# KitchenExhaustFan.net
KiCad netlist of a schematic drawn in EasyEDA
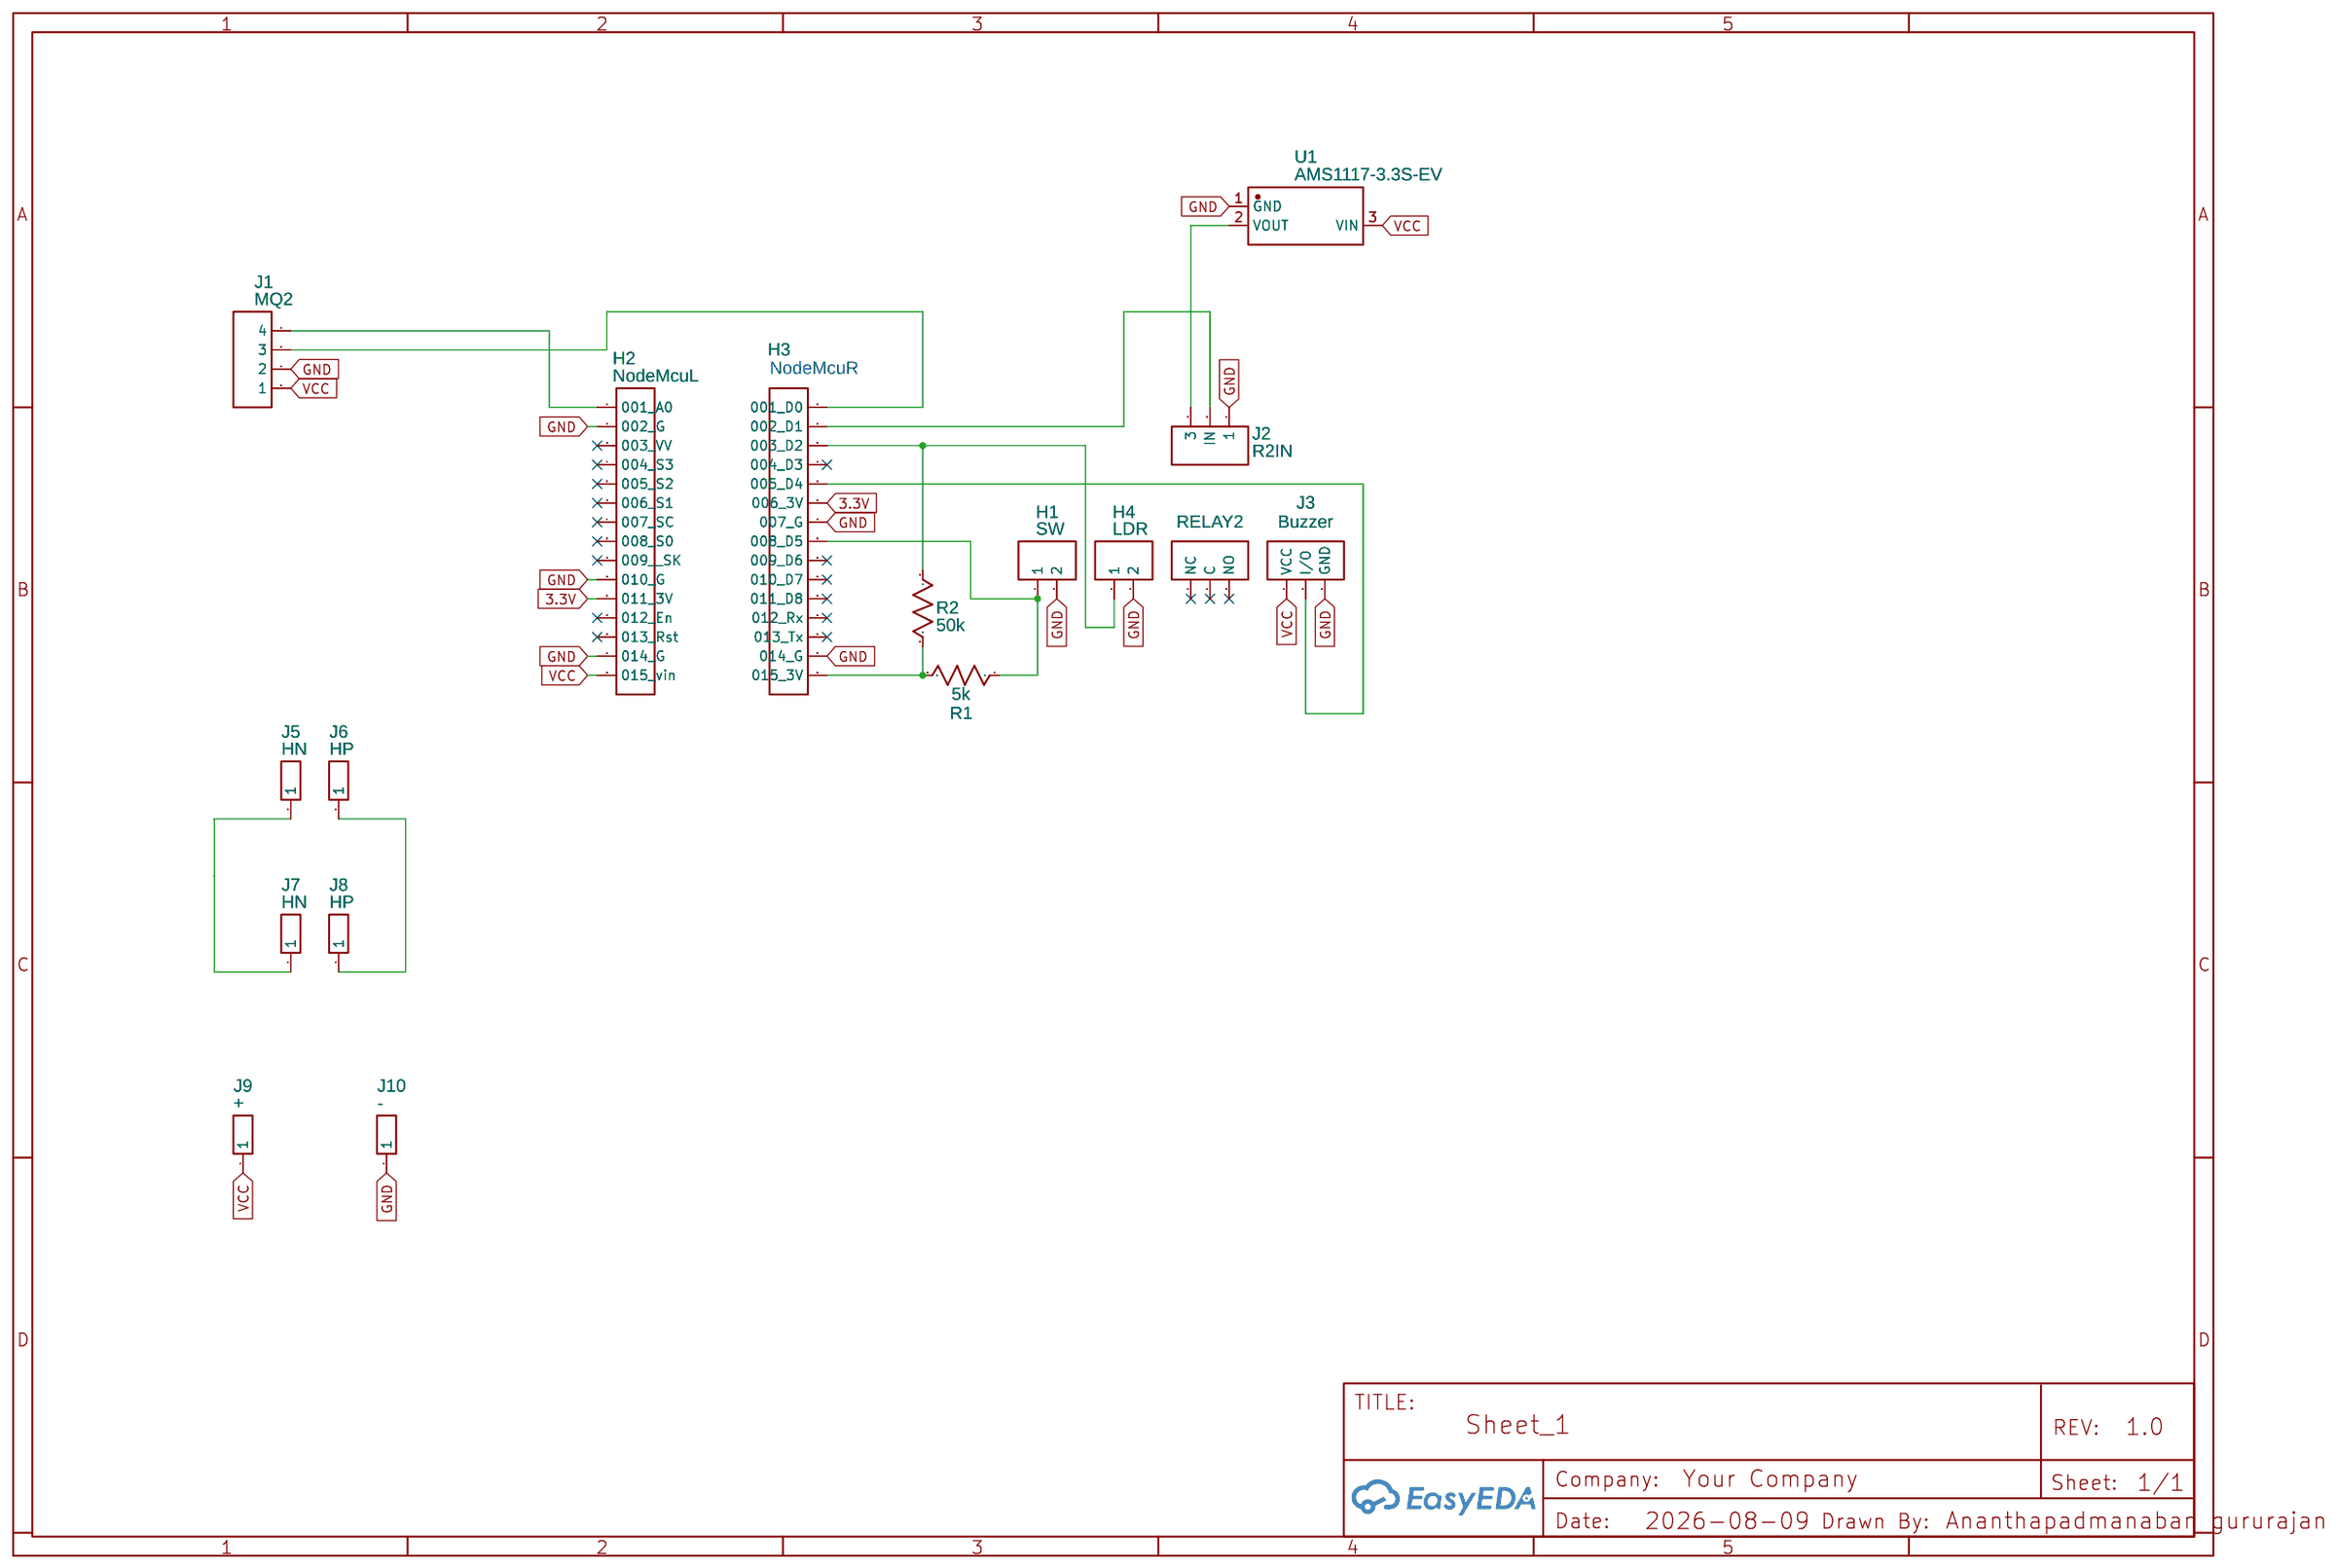
[diagram p0: schematic sheet]

(export (version "E")
  (design (tool "Eeschema 10.0.6"))
  (components
    (comp (ref "H1") (value "SW") (libsource (lib "") (part "HDR-F-2.54_1x2")))
    (comp (ref "H2") (value "NodeMcuL") (libsource (lib "") (part "HDR-F-2.54_1x15")))
    (comp (ref "H3") (value "NodeMcuR") (libsource (lib "") (part "HDR-F-2.54_1x15_1")))
    (comp (ref "H4") (value "LDR") (libsource (lib "") (part "HDR-F-2.54_1x2")))
    (comp (ref "J1") (value "MQ2") (libsource (lib "") (part "HDR-M-2.54_1x4")))
    (comp (ref "J2") (value "R2IN") (libsource (lib "") (part "HDR-M-2.54_1x3_1")))
    (comp (ref "J3") (value "Buzzer") (libsource (lib "") (part "HDR-M-2.54_1x3")))
    (comp (ref "J5") (value "HN") (libsource (lib "") (part "HDR-M-2.54_1x1")))
    (comp (ref "J6") (value "HP") (libsource (lib "") (part "HDR-M-2.54_1x1")))
    (comp (ref "J7") (value "HN") (libsource (lib "") (part "HDR-M-2.54_1x1")))
    (comp (ref "J8") (value "HP") (libsource (lib "") (part "HDR-M-2.54_1x1")))
    (comp (ref "J9") (value "+") (libsource (lib "") (part "HDR-M-2.54_1x1")))
    (comp (ref "J10") (value "-") (libsource (lib "") (part "HDR-M-2.54_1x1")))
    (comp (ref "R1") (value "5k") (libsource (lib "") (part "R_AXIAL-0.3_US_1")))
    (comp (ref "R2") (value "50k") (libsource (lib "") (part "R_AXIAL-0.3_US")))
    (comp (ref "RELAY2") (value "Relay1") (libsource (lib "") (part "HDR-M-2.54_1x3_2")))
    (comp (ref "U1") (value "AMS1117-3.3S-EV") (libsource (lib "") (part "AMS1117-3.3S-EV")))
  )
  (nets
    (net (code "1") (name "3.3V") (class "Default")
      (node (ref "H2") (pin "11") (pinfunction "011_3V_11") (pintype "unspecified"))
      (node (ref "H3") (pin "6") (pinfunction "006_3V_6") (pintype "unspecified"))
    )
    (net (code "2") (name "GND") (class "Default")
      (node (ref "H1") (pin "2") (pinfunction "2_2") (pintype "input"))
      (node (ref "H2") (pin "10") (pinfunction "010_G_10") (pintype "unspecified"))
      (node (ref "H2") (pin "14") (pinfunction "014_G_14") (pintype "unspecified"))
      (node (ref "H2") (pin "2") (pinfunction "002_G_2") (pintype "unspecified"))
      (node (ref "H3") (pin "14") (pinfunction "014_G_14") (pintype "unspecified"))
      (node (ref "H3") (pin "7") (pinfunction "007_G_7") (pintype "unspecified"))
      (node (ref "H4") (pin "2") (pinfunction "2_2") (pintype "input"))
      (node (ref "J1") (pin "2") (pinfunction "2_2") (pintype "unspecified"))
      (node (ref "J10") (pin "1") (pinfunction "1_1") (pintype "input"))
      (node (ref "J2") (pin "1") (pinfunction "1_1") (pintype "input"))
      (node (ref "J3") (pin "3") (pinfunction "GND_3") (pintype "input"))
      (node (ref "U1") (pin "1") (pinfunction "GND_1") (pintype "unspecified"))
    )
    (net (code "3") (name "Net-(H2-001_A0)") (class "Default")
      (node (ref "H2") (pin "1") (pinfunction "001_A0_1") (pintype "unspecified"))
      (node (ref "J1") (pin "4") (pinfunction "4_4") (pintype "unspecified"))
    )
    (net (code "4") (name "Net-(H3-001_D0)") (class "Default")
      (node (ref "H3") (pin "1") (pinfunction "001_D0_1") (pintype "unspecified"))
      (node (ref "J1") (pin "3") (pinfunction "3_3") (pintype "unspecified"))
    )
    (net (code "5") (name "Net-(H3-002_D1)") (class "Default")
      (node (ref "H3") (pin "2") (pinfunction "002_D1_2") (pintype "unspecified"))
      (node (ref "J2") (pin "2") (pinfunction "IN_2") (pintype "input"))
    )
    (net (code "6") (name "Net-(H3-003_D2)") (class "Default")
      (node (ref "H3") (pin "3") (pinfunction "003_D2_3") (pintype "unspecified"))
      (node (ref "H4") (pin "1") (pinfunction "1_1") (pintype "input"))
      (node (ref "R2") (pin "1") (pinfunction "1_1") (pintype "unspecified"))
    )
    (net (code "7") (name "Net-(H3-005_D4)") (class "Default")
      (node (ref "H3") (pin "5") (pinfunction "005_D4_5") (pintype "unspecified"))
      (node (ref "J3") (pin "2") (pinfunction "I/O_2") (pintype "input"))
    )
    (net (code "8") (name "Net-(H3-008_D5)") (class "Default")
      (node (ref "H1") (pin "1") (pinfunction "1_1") (pintype "input"))
      (node (ref "H3") (pin "8") (pinfunction "008_D5_8") (pintype "unspecified"))
      (node (ref "R1") (pin "1") (pinfunction "1_1") (pintype "unspecified"))
    )
    (net (code "9") (name "Net-(H3-015_3V)") (class "Default")
      (node (ref "H3") (pin "15") (pinfunction "015_3V_15") (pintype "unspecified"))
      (node (ref "R1") (pin "2") (pinfunction "2_2") (pintype "unspecified"))
      (node (ref "R2") (pin "2") (pinfunction "2_2") (pintype "unspecified"))
    )
    (net (code "10") (name "Net-(J5-Pad1)") (class "Default")
      (node (ref "J5") (pin "1") (pinfunction "1_1") (pintype "input"))
      (node (ref "J7") (pin "1") (pinfunction "1_1") (pintype "input"))
    )
    (net (code "11") (name "Net-(J6-Pad1)") (class "Default")
      (node (ref "J6") (pin "1") (pinfunction "1_1") (pintype "input"))
      (node (ref "J8") (pin "1") (pinfunction "1_1") (pintype "input"))
    )
    (net (code "12") (name "Net-(U1-VOUT)") (class "Default")
      (node (ref "J2") (pin "3") (pinfunction "3_3") (pintype "input"))
      (node (ref "U1") (pin "2") (pinfunction "VOUT_2") (pintype "unspecified"))
    )
    (net (code "13") (name "VCC") (class "Default")
      (node (ref "H2") (pin "15") (pinfunction "015_vin_15") (pintype "unspecified"))
      (node (ref "J1") (pin "1") (pinfunction "1_1") (pintype "unspecified"))
      (node (ref "J3") (pin "1") (pinfunction "VCC_1") (pintype "input"))
      (node (ref "J9") (pin "1") (pinfunction "1_1") (pintype "input"))
      (node (ref "U1") (pin "3") (pinfunction "VIN_3") (pintype "unspecified"))
    )
    (net (code "14") (name "unconnected-(H2-003_VV-Pad3)") (class "Default")
      (node (ref "H2") (pin "3") (pinfunction "003_VV_3") (pintype "unspecified+no_connect"))
    )
    (net (code "15") (name "unconnected-(H2-004_S3-Pad4)") (class "Default")
      (node (ref "H2") (pin "4") (pinfunction "004_S3_4") (pintype "unspecified+no_connect"))
    )
    (net (code "16") (name "unconnected-(H2-005_S2-Pad5)") (class "Default")
      (node (ref "H2") (pin "5") (pinfunction "005_S2_5") (pintype "unspecified+no_connect"))
    )
    (net (code "17") (name "unconnected-(H2-006_S1-Pad6)") (class "Default")
      (node (ref "H2") (pin "6") (pinfunction "006_S1_6") (pintype "unspecified+no_connect"))
    )
    (net (code "18") (name "unconnected-(H2-007_SC-Pad7)") (class "Default")
      (node (ref "H2") (pin "7") (pinfunction "007_SC_7") (pintype "unspecified+no_connect"))
    )
    (net (code "19") (name "unconnected-(H2-008_S0-Pad8)") (class "Default")
      (node (ref "H2") (pin "8") (pinfunction "008_S0_8") (pintype "unspecified+no_connect"))
    )
    (net (code "20") (name "unconnected-(H2-009__SK-Pad9)") (class "Default")
      (node (ref "H2") (pin "9") (pinfunction "009__SK_9") (pintype "unspecified+no_connect"))
    )
    (net (code "21") (name "unconnected-(H2-012_En-Pad12)") (class "Default")
      (node (ref "H2") (pin "12") (pinfunction "012_En_12") (pintype "unspecified+no_connect"))
    )
    (net (code "22") (name "unconnected-(H2-013_Rst-Pad13)") (class "Default")
      (node (ref "H2") (pin "13") (pinfunction "013_Rst_13") (pintype "unspecified+no_connect"))
    )
    (net (code "23") (name "unconnected-(H3-004_D3-Pad4)") (class "Default")
      (node (ref "H3") (pin "4") (pinfunction "004_D3_4") (pintype "unspecified+no_connect"))
    )
    (net (code "24") (name "unconnected-(H3-009_D6-Pad9)") (class "Default")
      (node (ref "H3") (pin "9") (pinfunction "009_D6_9") (pintype "unspecified+no_connect"))
    )
    (net (code "25") (name "unconnected-(H3-010_D7-Pad10)") (class "Default")
      (node (ref "H3") (pin "10") (pinfunction "010_D7_10") (pintype "unspecified+no_connect"))
    )
    (net (code "26") (name "unconnected-(H3-011_D8-Pad11)") (class "Default")
      (node (ref "H3") (pin "11") (pinfunction "011_D8_11") (pintype "unspecified+no_connect"))
    )
    (net (code "27") (name "unconnected-(H3-012_Rx-Pad12)") (class "Default")
      (node (ref "H3") (pin "12") (pinfunction "012_Rx_12") (pintype "unspecified+no_connect"))
    )
    (net (code "28") (name "unconnected-(H3-013_Tx-Pad13)") (class "Default")
      (node (ref "H3") (pin "13") (pinfunction "013_Tx_13") (pintype "unspecified+no_connect"))
    )
    (net (code "29") (name "unconnected-(RELAY2-C-Pad2)") (class "Default")
      (node (ref "RELAY2") (pin "2") (pinfunction "C_2") (pintype "input+no_connect"))
    )
    (net (code "30") (name "unconnected-(RELAY2-NC-Pad1)") (class "Default")
      (node (ref "RELAY2") (pin "1") (pinfunction "NC_1") (pintype "input+no_connect"))
    )
    (net (code "31") (name "unconnected-(RELAY2-NO-Pad3)") (class "Default")
      (node (ref "RELAY2") (pin "3") (pinfunction "NO_3") (pintype "input+no_connect"))
    )
  )
)
